# RF1.net
KiCad netlist of a schematic drawn in EAGLE
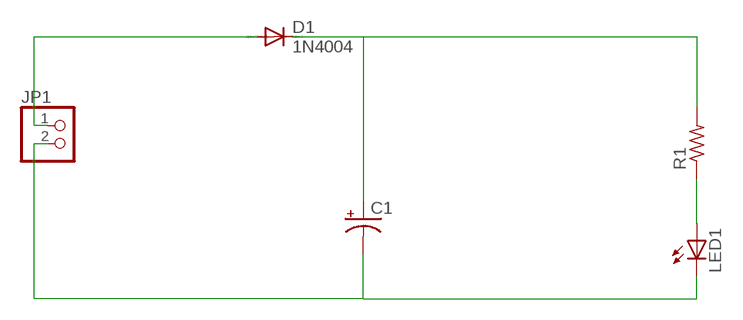
[diagram p0: schematic, sheet 1]

(export (version "E")
  (design (tool "Eeschema 10.0.6"))
  (components
    (comp (ref "C1")
      (value "CPOL-USE3.5-10")
      (footprint "eagle-import:E3,5-10")
      (libsource (lib "eagle-import") (part "CPOL-USE3.5-10"))
    )
    (comp (ref "D1")
      (value "1N4004")
      (footprint "eagle-import:DO41-10")
      (libsource (lib "eagle-import") (part "1N4004"))
    )
    (comp (ref "JP1")
      (value "PINHD-1X2")
      (footprint "eagle-import:1X02")
      (libsource (lib "eagle-import") (part "PINHD-1X2"))
    )
    (comp (ref "LED1")
      (value "LED5MM")
      (footprint "eagle-import:LED5MM")
      (libsource (lib "eagle-import") (part "LED5MM"))
    )
    (comp (ref "R1")
      (value "R-US_0207/10")
      (footprint "eagle-import:0207_10")
      (libsource (lib "eagle-import") (part "R-US_0207/10"))
    )
  )
  (nets
    (net (code "1") (name "Net-(C1-Pad+)") (class "Default")
      (node (ref "C1") (pin "+") (pinfunction "+_+") (pintype "passive"))
      (node (ref "D1") (pin "C") (pinfunction "C_C") (pintype "passive"))
      (node (ref "R1") (pin "2") (pinfunction "2_2") (pintype "passive"))
    )
    (net (code "2") (name "Net-(D1-PadA)") (class "Default")
      (node (ref "D1") (pin "A") (pinfunction "A_A") (pintype "passive"))
      (node (ref "JP1") (pin "1") (pinfunction "1_1") (pintype "passive"))
    )
    (net (code "3") (name "Net-(LED1-C)") (class "Default")
      (node (ref "C1") (pin "-") (pinfunction "-_-") (pintype "passive"))
      (node (ref "JP1") (pin "2") (pinfunction "2_2") (pintype "passive"))
      (node (ref "LED1") (pin "K") (pinfunction "C_K") (pintype "passive"))
    )
    (net (code "4") (name "Net-(LED1-PadA)") (class "Default")
      (node (ref "LED1") (pin "A") (pinfunction "A_A") (pintype "passive"))
      (node (ref "R1") (pin "1") (pinfunction "1_1") (pintype "passive"))
    )
  )
)
